# PWM_transmitter.net
KiCad netlist of a schematic drawn in EAGLE
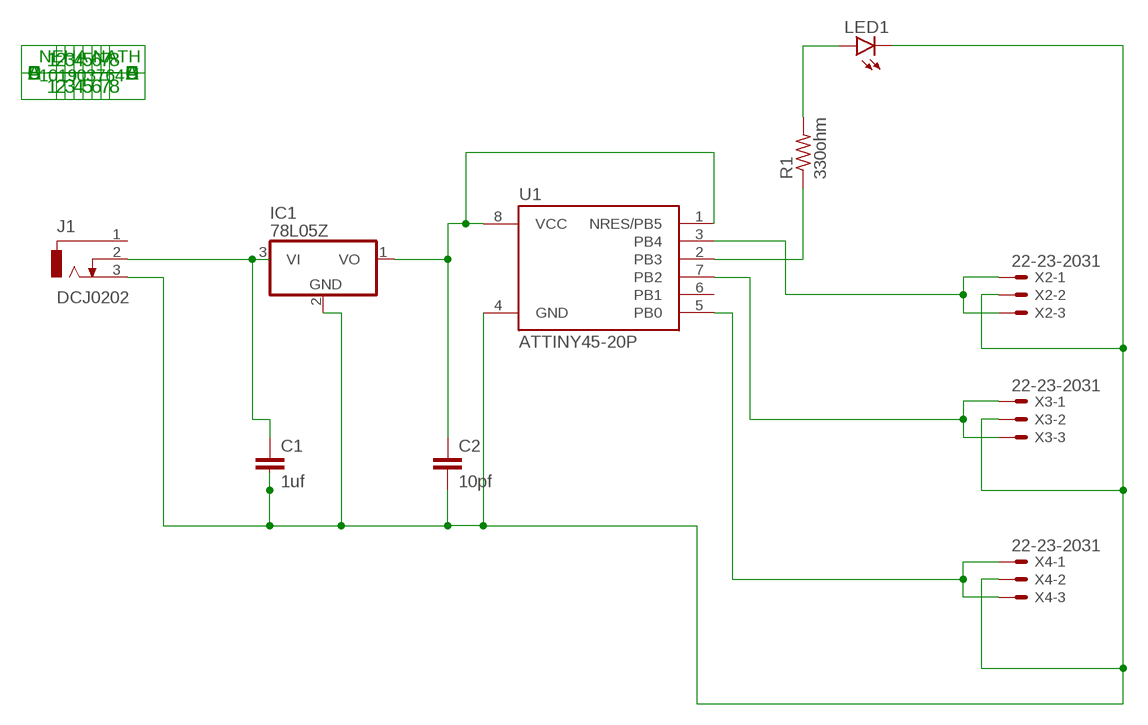
[diagram p0: schematic, sheet 1]

(export (version "E")
  (design (tool "Eeschema 10.0.6"))
  (components
    (comp (ref "C1")
      (value "1uf")
      (footprint "eagle-import:C2.5-2")
      (libsource (lib "eagle-import") (part "C2.5/2"))
    )
    (comp (ref "C2")
      (value "10pf")
      (footprint "eagle-import:C2.5-2")
      (libsource (lib "eagle-import") (part "C2.5/2"))
    )
    (comp (ref "IC1")
      (value "78L05Z")
      (footprint "eagle-import:TO92")
      (libsource (lib "eagle-import") (part "78ZL05"))
    )
    (comp (ref "J1")
      (value "DCJ0202")
      (footprint "eagle-import:DCJ0202")
      (libsource (lib "eagle-import") (part "DCJ0202"))
    )
    (comp (ref "LED1")
      (value "LED3MM")
      (footprint "eagle-import:LED3MM")
      (libsource (lib "eagle-import") (part "LED3MM"))
    )
    (comp (ref "R1")
      (value "330ohm")
      (footprint "eagle-import:0207_7")
      (libsource (lib "eagle-import") (part "R-US_0207/7"))
    )
    (comp (ref "U1")
      (value "ATTINY45-20P")
      (footprint "eagle-import:PDIP08_300MIL")
      (libsource (lib "eagle-import") (part "ATTINY45P-20"))
    )
    (comp (ref "X2")
      (value "22-23-2031")
      (footprint "eagle-import:22-23-2031")
      (fields (field (name "MF") "MOLEX"))
      (libsource (lib "eagle-import") (part "22-23-2031"))
    )
    (comp (ref "X3")
      (value "22-23-2031")
      (footprint "eagle-import:22-23-2031")
      (fields (field (name "MF") "MOLEX"))
      (libsource (lib "eagle-import") (part "22-23-2031"))
    )
    (comp (ref "X4")
      (value "22-23-2031")
      (footprint "eagle-import:22-23-2031")
      (fields (field (name "MF") "MOLEX"))
      (libsource (lib "eagle-import") (part "22-23-2031"))
    )
  )
  (nets
    (net (code "1") (name "Net-(IC1-GND)") (class "Default")
      (node (ref "C1") (pin "2") (pinfunction "2_2") (pintype "passive"))
      (node (ref "C2") (pin "2") (pinfunction "2_2") (pintype "passive"))
      (node (ref "IC1") (pin "2") (pinfunction "GND_2") (pintype "passive"))
      (node (ref "J1") (pin "3") (pinfunction "3_3") (pintype "passive"))
      (node (ref "LED1") (pin "K") (pinfunction "C_K") (pintype "passive"))
      (node (ref "U1") (pin "4") (pinfunction "GND_4") (pintype "power_in"))
      (node (ref "X2") (pin "2") (pinfunction "S_2") (pintype "passive"))
      (node (ref "X3") (pin "2") (pinfunction "S_2") (pintype "passive"))
      (node (ref "X4") (pin "2") (pinfunction "S_2") (pintype "passive"))
    )
    (net (code "2") (name "Net-(IC1-VI)") (class "Default")
      (node (ref "C1") (pin "1") (pinfunction "1_1") (pintype "passive"))
      (node (ref "IC1") (pin "3") (pinfunction "VI_3") (pintype "input"))
      (node (ref "J1") (pin "2") (pinfunction "2_2") (pintype "passive"))
    )
    (net (code "3") (name "Net-(IC1-VO)") (class "Default")
      (node (ref "C2") (pin "1") (pinfunction "1_1") (pintype "passive"))
      (node (ref "IC1") (pin "1") (pinfunction "VO_1") (pintype "passive"))
      (node (ref "U1") (pin "1") (pinfunction "NRES/PB5_1") (pintype "bidirectional"))
      (node (ref "U1") (pin "8") (pinfunction "VCC_8") (pintype "power_in"))
    )
    (net (code "4") (name "Net-(LED1-PadA)") (class "Default")
      (node (ref "LED1") (pin "A") (pinfunction "A_A") (pintype "passive"))
      (node (ref "R1") (pin "2") (pinfunction "2_2") (pintype "passive"))
    )
    (net (code "5") (name "Net-(U1-PB0)") (class "Default")
      (node (ref "U1") (pin "5") (pinfunction "PB0_5") (pintype "bidirectional"))
      (node (ref "X4") (pin "1") (pinfunction "S_1") (pintype "passive"))
      (node (ref "X4") (pin "3") (pinfunction "S_3") (pintype "passive"))
    )
    (net (code "6") (name "Net-(U1-PB2)") (class "Default")
      (node (ref "U1") (pin "7") (pinfunction "PB2_7") (pintype "bidirectional"))
      (node (ref "X3") (pin "1") (pinfunction "S_1") (pintype "passive"))
      (node (ref "X3") (pin "3") (pinfunction "S_3") (pintype "passive"))
    )
    (net (code "7") (name "Net-(U1-PB3)") (class "Default")
      (node (ref "R1") (pin "1") (pinfunction "1_1") (pintype "passive"))
      (node (ref "U1") (pin "2") (pinfunction "PB3_2") (pintype "bidirectional"))
    )
    (net (code "8") (name "Net-(U1-PB4)") (class "Default")
      (node (ref "U1") (pin "3") (pinfunction "PB4_3") (pintype "bidirectional"))
      (node (ref "X2") (pin "1") (pinfunction "S_1") (pintype "passive"))
      (node (ref "X2") (pin "3") (pinfunction "S_3") (pintype "passive"))
    )
    (net (code "9") (name "unconnected-(J1-Pad1)") (class "Default")
      (node (ref "J1") (pin "1") (pinfunction "1_1") (pintype "passive"))
    )
    (net (code "10") (name "unconnected-(U1-PB1-Pad6)") (class "Default")
      (node (ref "U1") (pin "6") (pinfunction "PB1_6") (pintype "bidirectional"))
    )
  )
)
